# 3_Relayv2.net
KiCad netlist of a schematic drawn in Altium Designer
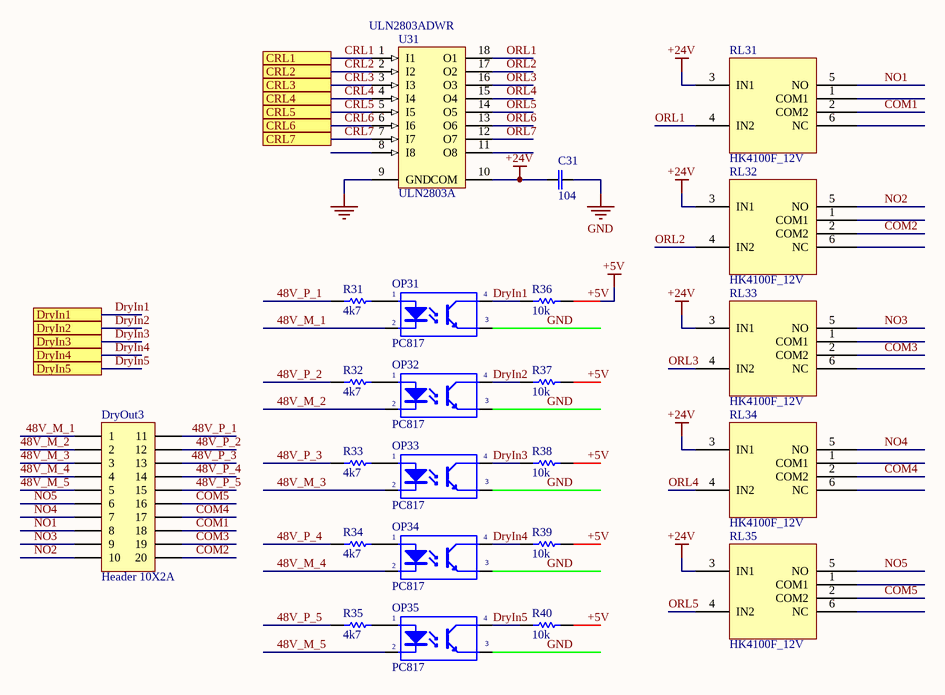
[diagram p0: 3.Relayv2.SchDoc]

(export (version "E")
  (design (tool "Eeschema 10.0.6"))
  (components
    (comp (ref "C31")
      (value "104")
      (footprint "swatpcblib:CAP 0805")
      (description "Capacitor non polarized")
      (fields (field (name "Comment") "Tụ điện dán 0805104"))
      (libsource (lib "Tuan") (part "CAP NP"))
    )
    (comp (ref "DryOut3")
      (value "Header 10X2A")
      (footprint "heromap:HDR2X10_CEN")
      (description "Header, 10-Pin, Dual row")
      (fields (field (name "PUBLISHER") "Altium Limited"))
      (libsource (lib "heromap") (part "Header 10X2A"))
    )
    (comp (ref "OP31")
      (value "PC817")
      (footprint "hayqua:DIP4/W0.3")
      (description "Single Opto")
      (libsource (lib "syhaunguyen") (part "PC817"))
    )
    (comp (ref "OP32")
      (value "PC817")
      (footprint "hayqua:DIP4/W0.3")
      (description "Single Opto")
      (libsource (lib "syhaunguyen") (part "PC817"))
    )
    (comp (ref "OP33")
      (value "PC817")
      (footprint "hayqua:DIP4/W0.3")
      (description "Single Opto")
      (libsource (lib "syhaunguyen") (part "PC817"))
    )
    (comp (ref "OP34")
      (value "PC817")
      (footprint "hayqua:DIP4/W0.3")
      (description "Single Opto")
      (libsource (lib "syhaunguyen") (part "PC817"))
    )
    (comp (ref "OP35")
      (value "PC817")
      (footprint "hayqua:DIP4/W0.3")
      (description "Single Opto")
      (libsource (lib "syhaunguyen") (part "PC817"))
    )
    (comp (ref "R31")
      (value "4k7")
      (footprint "PBL - SMD Packages:RESC3216N")
      (description "Resistor")
      (fields (field (name "Comment") "Điện trở dán 12064k7"))
      (libsource (lib "Tuan") (part "Res"))
    )
    (comp (ref "R32")
      (value "4k7")
      (footprint "PBL - SMD Packages:RESC3216N")
      (description "Resistor")
      (fields (field (name "Comment") "Điện trở dán 12064k7"))
      (libsource (lib "Tuan") (part "Res"))
    )
    (comp (ref "R33")
      (value "4k7")
      (footprint "PBL - SMD Packages:RESC3216N")
      (description "Resistor")
      (fields (field (name "Comment") "Điện trở dán 12064k7"))
      (libsource (lib "Tuan") (part "Res"))
    )
    (comp (ref "R34")
      (value "4k7")
      (footprint "PBL - SMD Packages:RESC3216N")
      (description "Resistor")
      (fields (field (name "Comment") "Điện trở dán 12064k7"))
      (libsource (lib "Tuan") (part "Res"))
    )
    (comp (ref "R35")
      (value "4k7")
      (footprint "PBL - SMD Packages:RESC3216N")
      (description "Resistor")
      (fields (field (name "Comment") "Điện trở dán 12064k7"))
      (libsource (lib "Tuan") (part "Res"))
    )
    (comp (ref "R36")
      (value "10k")
      (footprint "swatpcblib:RES 0805")
      (description "Resistor")
      (fields (field (name "Comment") "Điện trở dán 080510k"))
      (libsource (lib "Tuan") (part "Res"))
    )
    (comp (ref "R37")
      (value "10k")
      (footprint "swatpcblib:RES 0805")
      (description "Resistor")
      (fields (field (name "Comment") "Điện trở dán 080510k"))
      (libsource (lib "Tuan") (part "Res"))
    )
    (comp (ref "R38")
      (value "10k")
      (footprint "swatpcblib:RES 0805")
      (description "Resistor")
      (fields (field (name "Comment") "Điện trở dán 080510k"))
      (libsource (lib "Tuan") (part "Res"))
    )
    (comp (ref "R39")
      (value "10k")
      (footprint "swatpcblib:RES 0805")
      (description "Resistor")
      (fields (field (name "Comment") "Điện trở dán 080510k"))
      (libsource (lib "Tuan") (part "Res"))
    )
    (comp (ref "R40")
      (value "10k")
      (footprint "swatpcblib:RES 0805")
      (description "Resistor")
      (fields (field (name "Comment") "Điện trở dán 080510k"))
      (libsource (lib "Tuan") (part "Res"))
    )
    (comp (ref "RL31") (value "HK4100F_12V") (footprint "HK4100F") (libsource (lib "Tuan") (part "HK4100F")))
    (comp (ref "RL32") (value "HK4100F_12V") (footprint "HK4100F") (libsource (lib "Tuan") (part "HK4100F")))
    (comp (ref "RL33") (value "HK4100F_12V") (footprint "HK4100F") (libsource (lib "Tuan") (part "HK4100F")))
    (comp (ref "RL34") (value "HK4100F_12V") (footprint "HK4100F") (libsource (lib "Tuan") (part "HK4100F")))
    (comp (ref "RL35") (value "HK4100F_12V") (footprint "HK4100F") (libsource (lib "Tuan") (part "HK4100F")))
    (comp (ref "U31")
      (value "ULN2803A")
      (footprint "SOIC-18")
      (description "High-Voltage, High-Current Darlington Array")
      (fields
        (field (name "SUPPLIER PART NUMBER 1") "ULN2803ADWR")
        (field (name "MANUFACTURER") "Texas Instruments")
        (field (name "MANUFACTURER PART NUMBER") "ULN2803ADWR")
        (field (name "PUBLISHER") "Altium Limited")
      )
      (libsource (lib "syhaunguyen") (part "ULN2803A"))
    )
  )
  (nets
    (net (code "1") (name "+5V") (class "Default")
      (node (ref "R36") (pin "2") (pinfunction "2_2") (pintype "passive"))
      (node (ref "R37") (pin "2") (pinfunction "2_2") (pintype "passive"))
      (node (ref "R38") (pin "2") (pinfunction "2_2") (pintype "passive"))
      (node (ref "R39") (pin "2") (pinfunction "2_2") (pintype "passive"))
      (node (ref "R40") (pin "2") (pinfunction "2_2") (pintype "passive"))
    )
    (net (code "2") (name "+24V") (class "Default")
      (node (ref "C31") (pin "2") (pinfunction "2_2") (pintype "passive"))
      (node (ref "RL31") (pin "3") (pinfunction "IN1_3") (pintype "passive"))
      (node (ref "RL32") (pin "3") (pinfunction "IN1_3") (pintype "passive"))
      (node (ref "RL33") (pin "3") (pinfunction "IN1_3") (pintype "passive"))
      (node (ref "RL34") (pin "3") (pinfunction "IN1_3") (pintype "passive"))
      (node (ref "RL35") (pin "3") (pinfunction "IN1_3") (pintype "passive"))
      (node (ref "U31") (pin "10") (pinfunction "COM_10") (pintype "passive"))
    )
    (net (code "3") (name "/48V_M_1") (class "Default")
      (node (ref "DryOut3") (pin "1") (pinfunction "1_1") (pintype "passive"))
      (node (ref "OP31") (pin "2") (pinfunction "K_2") (pintype "passive"))
    )
    (net (code "4") (name "/48V_M_2") (class "Default")
      (node (ref "DryOut3") (pin "2") (pinfunction "2_2") (pintype "passive"))
      (node (ref "OP32") (pin "2") (pinfunction "K_2") (pintype "passive"))
    )
    (net (code "5") (name "/48V_M_3") (class "Default")
      (node (ref "DryOut3") (pin "3") (pinfunction "3_3") (pintype "passive"))
      (node (ref "OP33") (pin "2") (pinfunction "K_2") (pintype "passive"))
    )
    (net (code "6") (name "/48V_M_4") (class "Default")
      (node (ref "DryOut3") (pin "4") (pinfunction "4_4") (pintype "passive"))
      (node (ref "OP34") (pin "2") (pinfunction "K_2") (pintype "passive"))
    )
    (net (code "7") (name "/48V_M_5") (class "Default")
      (node (ref "DryOut3") (pin "5") (pinfunction "5_5") (pintype "passive"))
      (node (ref "OP35") (pin "2") (pinfunction "K_2") (pintype "passive"))
    )
    (net (code "8") (name "/48V_P_1") (class "Default")
      (node (ref "DryOut3") (pin "11") (pinfunction "11_11") (pintype "passive"))
      (node (ref "R31") (pin "1") (pinfunction "1_1") (pintype "passive"))
    )
    (net (code "9") (name "/48V_P_2") (class "Default")
      (node (ref "DryOut3") (pin "12") (pinfunction "12_12") (pintype "passive"))
      (node (ref "R32") (pin "1") (pinfunction "1_1") (pintype "passive"))
    )
    (net (code "10") (name "/48V_P_3") (class "Default")
      (node (ref "DryOut3") (pin "13") (pinfunction "13_13") (pintype "passive"))
      (node (ref "R33") (pin "1") (pinfunction "1_1") (pintype "passive"))
    )
    (net (code "11") (name "/48V_P_4") (class "Default")
      (node (ref "DryOut3") (pin "14") (pinfunction "14_14") (pintype "passive"))
      (node (ref "R34") (pin "1") (pinfunction "1_1") (pintype "passive"))
    )
    (net (code "12") (name "/48V_P_5") (class "Default")
      (node (ref "DryOut3") (pin "15") (pinfunction "15_15") (pintype "passive"))
      (node (ref "R35") (pin "1") (pinfunction "1_1") (pintype "passive"))
    )
    (net (code "13") (name "/COM1") (class "Default")
      (node (ref "DryOut3") (pin "18") (pinfunction "18_18") (pintype "passive"))
      (node (ref "RL31") (pin "2") (pinfunction "COM2_2") (pintype "passive"))
    )
    (net (code "14") (name "/COM2") (class "Default")
      (node (ref "DryOut3") (pin "20") (pinfunction "20_20") (pintype "passive"))
      (node (ref "RL32") (pin "2") (pinfunction "COM2_2") (pintype "passive"))
    )
    (net (code "15") (name "/COM3") (class "Default")
      (node (ref "DryOut3") (pin "19") (pinfunction "19_19") (pintype "passive"))
      (node (ref "RL33") (pin "2") (pinfunction "COM2_2") (pintype "passive"))
    )
    (net (code "16") (name "/COM4") (class "Default")
      (node (ref "DryOut3") (pin "17") (pinfunction "17_17") (pintype "passive"))
      (node (ref "RL34") (pin "2") (pinfunction "COM2_2") (pintype "passive"))
    )
    (net (code "17") (name "/COM5") (class "Default")
      (node (ref "DryOut3") (pin "16") (pinfunction "16_16") (pintype "passive"))
      (node (ref "RL35") (pin "2") (pinfunction "COM2_2") (pintype "passive"))
    )
    (net (code "18") (name "/CRL1") (class "Default")
      (node (ref "U31") (pin "1") (pinfunction "I1_1") (pintype "input"))
    )
    (net (code "19") (name "/CRL2") (class "Default")
      (node (ref "U31") (pin "2") (pinfunction "I2_2") (pintype "input"))
    )
    (net (code "20") (name "/CRL3") (class "Default")
      (node (ref "U31") (pin "3") (pinfunction "I3_3") (pintype "input"))
    )
    (net (code "21") (name "/CRL4") (class "Default")
      (node (ref "U31") (pin "4") (pinfunction "I4_4") (pintype "input"))
    )
    (net (code "22") (name "/CRL5") (class "Default")
      (node (ref "U31") (pin "5") (pinfunction "I5_5") (pintype "input"))
    )
    (net (code "23") (name "/CRL6") (class "Default")
      (node (ref "U31") (pin "6") (pinfunction "I6_6") (pintype "input"))
    )
    (net (code "24") (name "/CRL7") (class "Default")
      (node (ref "U31") (pin "7") (pinfunction "I7_7") (pintype "input"))
    )
    (net (code "25") (name "/DryIn1") (class "Default")
      (node (ref "OP31") (pin "4") (pinfunction "C_4") (pintype "passive"))
      (node (ref "R36") (pin "1") (pinfunction "1_1") (pintype "passive"))
    )
    (net (code "26") (name "/DryIn2") (class "Default")
      (node (ref "OP32") (pin "4") (pinfunction "C_4") (pintype "passive"))
      (node (ref "R37") (pin "1") (pinfunction "1_1") (pintype "passive"))
    )
    (net (code "27") (name "/DryIn3") (class "Default")
      (node (ref "OP33") (pin "4") (pinfunction "C_4") (pintype "passive"))
      (node (ref "R38") (pin "1") (pinfunction "1_1") (pintype "passive"))
    )
    (net (code "28") (name "/DryIn4") (class "Default")
      (node (ref "OP34") (pin "4") (pinfunction "C_4") (pintype "passive"))
      (node (ref "R39") (pin "1") (pinfunction "1_1") (pintype "passive"))
    )
    (net (code "29") (name "/DryIn5") (class "Default")
      (node (ref "OP35") (pin "4") (pinfunction "C_4") (pintype "passive"))
      (node (ref "R40") (pin "1") (pinfunction "1_1") (pintype "passive"))
    )
    (net (code "30") (name "/NO1") (class "Default")
      (node (ref "DryOut3") (pin "8") (pinfunction "8_8") (pintype "passive"))
      (node (ref "RL31") (pin "5") (pinfunction "NO_5") (pintype "passive"))
    )
    (net (code "31") (name "/NO2") (class "Default")
      (node (ref "DryOut3") (pin "10") (pinfunction "10_10") (pintype "passive"))
      (node (ref "RL32") (pin "5") (pinfunction "NO_5") (pintype "passive"))
    )
    (net (code "32") (name "/NO3") (class "Default")
      (node (ref "DryOut3") (pin "9") (pinfunction "9_9") (pintype "passive"))
      (node (ref "RL33") (pin "5") (pinfunction "NO_5") (pintype "passive"))
    )
    (net (code "33") (name "/NO4") (class "Default")
      (node (ref "DryOut3") (pin "7") (pinfunction "7_7") (pintype "passive"))
      (node (ref "RL34") (pin "5") (pinfunction "NO_5") (pintype "passive"))
    )
    (net (code "34") (name "/NO5") (class "Default")
      (node (ref "DryOut3") (pin "6") (pinfunction "6_6") (pintype "passive"))
      (node (ref "RL35") (pin "5") (pinfunction "NO_5") (pintype "passive"))
    )
    (net (code "35") (name "/ORL1") (class "Default")
      (node (ref "RL31") (pin "4") (pinfunction "IN2_4") (pintype "passive"))
      (node (ref "U31") (pin "18") (pinfunction "O1_18") (pintype "open_collector"))
    )
    (net (code "36") (name "/ORL2") (class "Default")
      (node (ref "RL32") (pin "4") (pinfunction "IN2_4") (pintype "passive"))
      (node (ref "U31") (pin "17") (pinfunction "O2_17") (pintype "open_collector"))
    )
    (net (code "37") (name "/ORL3") (class "Default")
      (node (ref "RL33") (pin "4") (pinfunction "IN2_4") (pintype "passive"))
      (node (ref "U31") (pin "16") (pinfunction "O3_16") (pintype "open_collector"))
    )
    (net (code "38") (name "/ORL4") (class "Default")
      (node (ref "RL34") (pin "4") (pinfunction "IN2_4") (pintype "passive"))
      (node (ref "U31") (pin "15") (pinfunction "O4_15") (pintype "open_collector"))
    )
    (net (code "39") (name "/ORL5") (class "Default")
      (node (ref "RL35") (pin "4") (pinfunction "IN2_4") (pintype "passive"))
      (node (ref "U31") (pin "14") (pinfunction "O5_14") (pintype "open_collector"))
    )
    (net (code "40") (name "/ORL6") (class "Default")
      (node (ref "U31") (pin "13") (pinfunction "O6_13") (pintype "open_collector"))
    )
    (net (code "41") (name "/ORL7") (class "Default")
      (node (ref "U31") (pin "12") (pinfunction "O7_12") (pintype "open_collector"))
    )
    (net (code "42") (name "GND") (class "Default")
      (node (ref "C31") (pin "1") (pinfunction "1_1") (pintype "passive"))
      (node (ref "OP31") (pin "3") (pinfunction "E_3") (pintype "passive"))
      (node (ref "OP32") (pin "3") (pinfunction "E_3") (pintype "passive"))
      (node (ref "OP33") (pin "3") (pinfunction "E_3") (pintype "passive"))
      (node (ref "OP34") (pin "3") (pinfunction "E_3") (pintype "passive"))
      (node (ref "OP35") (pin "3") (pinfunction "E_3") (pintype "passive"))
      (node (ref "U31") (pin "9") (pinfunction "GND_9") (pintype "power_in"))
    )
    (net (code "43") (name "Net-(OP31-A)") (class "Default")
      (node (ref "OP31") (pin "1") (pinfunction "A_1") (pintype "passive"))
      (node (ref "R31") (pin "2") (pinfunction "2_2") (pintype "passive"))
    )
    (net (code "44") (name "Net-(OP32-A)") (class "Default")
      (node (ref "OP32") (pin "1") (pinfunction "A_1") (pintype "passive"))
      (node (ref "R32") (pin "2") (pinfunction "2_2") (pintype "passive"))
    )
    (net (code "45") (name "Net-(OP33-A)") (class "Default")
      (node (ref "OP33") (pin "1") (pinfunction "A_1") (pintype "passive"))
      (node (ref "R33") (pin "2") (pinfunction "2_2") (pintype "passive"))
    )
    (net (code "46") (name "Net-(OP34-A)") (class "Default")
      (node (ref "OP34") (pin "1") (pinfunction "A_1") (pintype "passive"))
      (node (ref "R34") (pin "2") (pinfunction "2_2") (pintype "passive"))
    )
    (net (code "47") (name "Net-(OP35-A)") (class "Default")
      (node (ref "OP35") (pin "1") (pinfunction "A_1") (pintype "passive"))
      (node (ref "R35") (pin "2") (pinfunction "2_2") (pintype "passive"))
    )
    (net (code "48") (name "unconnected-(RL31-COM1-Pad1)") (class "Default")
      (node (ref "RL31") (pin "1") (pinfunction "COM1_1") (pintype "passive"))
    )
    (net (code "49") (name "unconnected-(RL31-NC-Pad6)") (class "Default")
      (node (ref "RL31") (pin "6") (pinfunction "NC_6") (pintype "passive"))
    )
    (net (code "50") (name "unconnected-(RL32-COM1-Pad1)") (class "Default")
      (node (ref "RL32") (pin "1") (pinfunction "COM1_1") (pintype "passive"))
    )
    (net (code "51") (name "unconnected-(RL32-NC-Pad6)") (class "Default")
      (node (ref "RL32") (pin "6") (pinfunction "NC_6") (pintype "passive"))
    )
    (net (code "52") (name "unconnected-(RL33-COM1-Pad1)") (class "Default")
      (node (ref "RL33") (pin "1") (pinfunction "COM1_1") (pintype "passive"))
    )
    (net (code "53") (name "unconnected-(RL33-NC-Pad6)") (class "Default")
      (node (ref "RL33") (pin "6") (pinfunction "NC_6") (pintype "passive"))
    )
    (net (code "54") (name "unconnected-(RL34-COM1-Pad1)") (class "Default")
      (node (ref "RL34") (pin "1") (pinfunction "COM1_1") (pintype "passive"))
    )
    (net (code "55") (name "unconnected-(RL34-NC-Pad6)") (class "Default")
      (node (ref "RL34") (pin "6") (pinfunction "NC_6") (pintype "passive"))
    )
    (net (code "56") (name "unconnected-(RL35-COM1-Pad1)") (class "Default")
      (node (ref "RL35") (pin "1") (pinfunction "COM1_1") (pintype "passive"))
    )
    (net (code "57") (name "unconnected-(RL35-NC-Pad6)") (class "Default")
      (node (ref "RL35") (pin "6") (pinfunction "NC_6") (pintype "passive"))
    )
    (net (code "58") (name "unconnected-(U31-I8-Pad8)") (class "Default")
      (node (ref "U31") (pin "8") (pinfunction "I8_8") (pintype "input"))
    )
    (net (code "59") (name "unconnected-(U31-O8-Pad11)") (class "Default")
      (node (ref "U31") (pin "11") (pinfunction "O8_11") (pintype "open_collector"))
    )
  )
)
